# Echode.net
KiCad netlist of a schematic drawn in Altium Designer
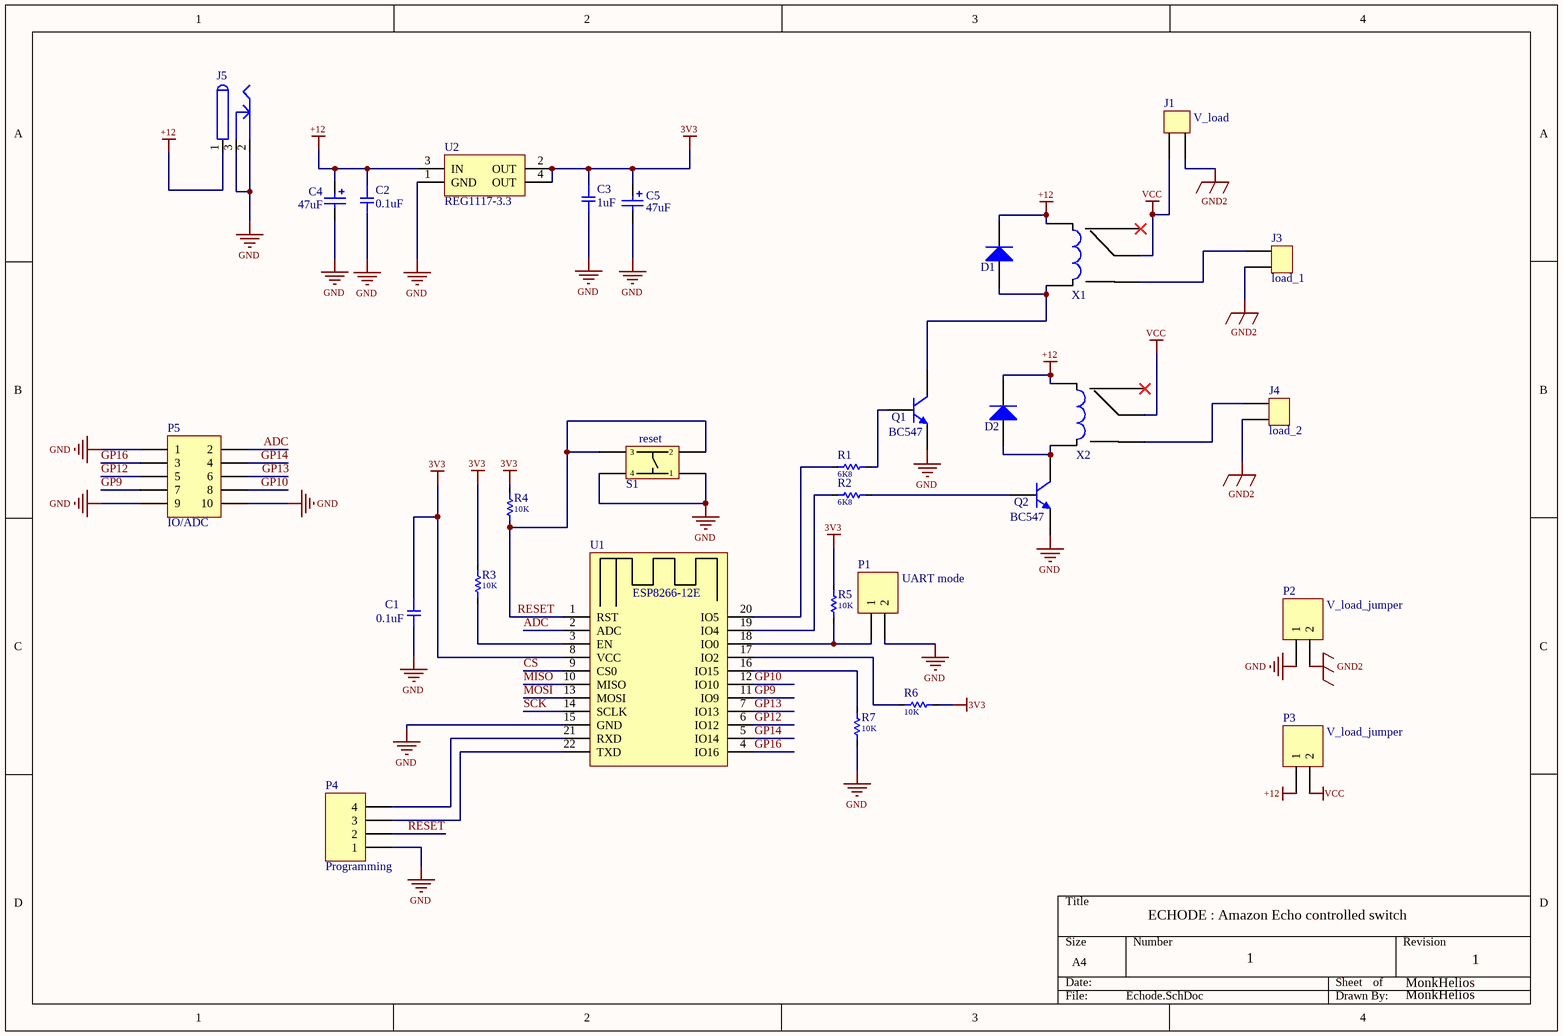
[diagram p0: Echode.SchDoc]

(export (version "E")
  (design (tool "Eeschema 10.0.6"))
  (components
    (comp (ref "C1")
      (value "0.1uF")
      (footprint "SMD-0805C")
      (description "CAP CER 10000PF 250V X7T 0805")
      (fields
        (field (name "DIGI-KEY PART NUMBER") "490-13986-1-ND")
        (field (name "PART NUMBER") "GC321AD72E103KX01D")
      )
      (libsource (lib "capacitor_murata_0805") (part "GC321AD72E103KX01D"))
    )
    (comp (ref "C2")
      (value "0.1uF")
      (footprint "SMD-0805C")
      (description "CAP CER 10000PF 250V X7T 0805")
      (fields
        (field (name "DIGI-KEY PART NUMBER") "490-13986-1-ND")
        (field (name "PART NUMBER") "GC321AD72E103KX01D")
      )
      (libsource (lib "capacitor_murata_0805") (part "GC321AD72E103KX01D"))
    )
    (comp (ref "C3")
      (value "1uF")
      (footprint "SMD-0805C")
      (description "CAP CER 10000PF 250V X7T 0805")
      (fields
        (field (name "DIGI-KEY PART NUMBER") "490-13986-1-ND")
        (field (name "PART NUMBER") "GC321AD72E103KX01D")
      )
      (libsource (lib "capacitor_murata_0805") (part "GC321AD72E103KX01D"))
    )
    (comp (ref "C4")
      (value "47uF")
      (footprint "PCBComponent_1")
      (libsource (lib "cap_pol") (part "Component_1"))
    )
    (comp (ref "C5")
      (value "47uF")
      (footprint "PCBComponent_1")
      (libsource (lib "cap_pol") (part "Component_1"))
    )
    (comp (ref "D1")
      (value "Diode 1N4007")
      (footprint "DO-41")
      (description "1 Amp General Purpose Rectifier")
      (fields (field (name "PUBLISHER") "Altium Limited"))
      (libsource (lib "Miscellaneous Devices") (part "Diode 1N4007"))
    )
    (comp (ref "D2")
      (value "Diode 1N4007")
      (footprint "DO-41")
      (description "1 Amp General Purpose Rectifier")
      (fields (field (name "PUBLISHER") "Altium Limited"))
      (libsource (lib "Miscellaneous Devices") (part "Diode 1N4007"))
    )
    (comp (ref "J1")
      (value "V_load")
      (footprint "Degson_DG126-5.0-02P-14")
      (libsource (lib "Degson_DG126-5.0-02P-14_Screw_Terminal") (part "Component_1"))
    )
    (comp (ref "J3")
      (value "load_1")
      (footprint "Degson_DG126-5.0-02P-14")
      (libsource (lib "") (part "Component_1_1"))
    )
    (comp (ref "J4")
      (value "load_2")
      (footprint "Degson_DG126-5.0-02P-14")
      (libsource (lib "") (part "Component_1_1"))
    )
    (comp (ref "J5")
      (value "PWR2.5")
      (footprint "KLD-0202")
      (description "Low Voltage Power Supply Connector")
      (fields (field (name "PUBLISHER") "Altium Limited"))
      (libsource (lib "Miscellaneous Connectors") (part "PWR2.5"))
    )
    (comp (ref "P1")
      (value "UART mode")
      (footprint "HDR1X2")
      (description "Header, 2-Pin")
      (fields (field (name "PUBLISHER") "Altium Limited"))
      (libsource (lib "Miscellaneous Connectors") (part "Header 2"))
    )
    (comp (ref "P2")
      (value "V_load_jumper")
      (footprint "HDR1X2")
      (description "Header, 2-Pin")
      (fields (field (name "PUBLISHER") "Altium Limited"))
      (libsource (lib "Miscellaneous Connectors") (part "Header 2"))
    )
    (comp (ref "P3")
      (value "V_load_jumper")
      (footprint "HDR1X2")
      (description "Header, 2-Pin")
      (fields (field (name "PUBLISHER") "Altium Limited"))
      (libsource (lib "Miscellaneous Connectors") (part "Header 2"))
    )
    (comp (ref "P4")
      (value "Programming")
      (footprint "HDR1X4")
      (description "Header, 4-Pin")
      (fields (field (name "PUBLISHER") "Altium Limited"))
      (libsource (lib "Miscellaneous Connectors") (part "Header 4"))
    )
    (comp (ref "P5")
      (value "IO/ADC")
      (footprint "HDR2X5")
      (description "Header, 5-Pin, Dual row")
      (fields (field (name "PUBLISHER") "Altium Limited"))
      (libsource (lib "Miscellaneous Connectors") (part "Header 5X2"))
    )
    (comp (ref "Q1")
      (value "BC547")
      (footprint "SOT-23B_N")
      (description "NPN Bipolar Transistor")
      (fields (field (name "PUBLISHER") "Altium Limited"))
      (libsource (lib "Miscellaneous Devices") (part "QNPN"))
    )
    (comp (ref "Q2")
      (value "BC547")
      (footprint "SOT-23B_N")
      (description "NPN Bipolar Transistor")
      (fields (field (name "PUBLISHER") "Altium Limited"))
      (libsource (lib "Miscellaneous Devices") (part "QNPN"))
    )
    (comp (ref "R1")
      (value "Component_1")
      (footprint "Resistor_0805")
      (fields (field (name "ALTIUM_UNNAMED_1") "6K8"))
      (libsource (lib "res") (part "Component_1"))
    )
    (comp (ref "R2")
      (value "Component_1")
      (footprint "Resistor_0805")
      (fields (field (name "ALTIUM_UNNAMED_1") "6K8"))
      (libsource (lib "res") (part "Component_1"))
    )
    (comp (ref "R3")
      (value "Component_1")
      (footprint "Resistor_0805")
      (fields (field (name "ALTIUM_UNNAMED_1") "10K"))
      (libsource (lib "res") (part "Component_1"))
    )
    (comp (ref "R4")
      (value "Component_1")
      (footprint "Resistor_0805")
      (fields (field (name "ALTIUM_UNNAMED_1") "10K"))
      (libsource (lib "res") (part "Component_1"))
    )
    (comp (ref "R5")
      (value "Component_1")
      (footprint "Resistor_0805")
      (fields (field (name "ALTIUM_UNNAMED_1") "10K"))
      (libsource (lib "res") (part "Component_1"))
    )
    (comp (ref "R6")
      (value "Component_1")
      (footprint "Resistor_0805")
      (fields (field (name "ALTIUM_UNNAMED_1") "10K"))
      (libsource (lib "res") (part "Component_1"))
    )
    (comp (ref "R7")
      (value "Component_1")
      (footprint "Resistor_0805")
      (fields (field (name "ALTIUM_UNNAMED_1") "10K"))
      (libsource (lib "res") (part "Component_1"))
    )
    (comp (ref "S1")
      (value "reset")
      (footprint "PCBComponent_1")
      (libsource (lib "panasonic_90deg_tactile") (part "Component_1"))
    )
    (comp (ref "U1")
      (value "ESP8266-12E")
      (footprint "PCBComponent_1")
      (libsource (lib "ESP8266-12E") (part "ESP8266-12E"))
    )
    (comp (ref "U2")
      (value "REG1117-3.3")
      (footprint "ZZ311")
      (description "800mA and 1A Low Dropout Positive Regulator 2.85V, 3.3V, 5V, and Adjustable")
      (fields (field (name "PUBLISHER") "Altium Limited"))
      (libsource (lib "BB Power Mgt Voltage Regulator") (part "REG1117-3.3"))
    )
    (comp (ref "X1") (value "~") (footprint "845HN-1C-C") (libsource (lib "845HN-1C-C") (part "845HN-1C-C")))
    (comp (ref "X2") (value "~") (footprint "845HN-1C-C") (libsource (lib "845HN-1C-C") (part "845HN-1C-C")))
  )
  (nets
    (net (code "1") (name "+12") (class "Default")
      (node (ref "C2") (pin "1") (pinfunction "1_1") (pintype "passive"))
      (node (ref "C4") (pin "1") (pinfunction "1_1") (pintype "passive"))
      (node (ref "D1") (pin "2") (pinfunction "K_2") (pintype "passive"))
      (node (ref "D2") (pin "2") (pinfunction "K_2") (pintype "passive"))
      (node (ref "J5") (pin "1") (pinfunction "1_1") (pintype "power_in"))
      (node (ref "P3") (pin "1") (pinfunction "1_1") (pintype "passive"))
      (node (ref "U2") (pin "3") (pinfunction "IN_3") (pintype "power_in"))
      (node (ref "X1") (pin "1") (pinfunction "1_1") (pintype "passive"))
      (node (ref "X2") (pin "1") (pinfunction "1_1") (pintype "passive"))
    )
    (net (code "2") (name "/ADC") (class "Default")
      (node (ref "P5") (pin "2") (pinfunction "2_2") (pintype "passive"))
      (node (ref "U1") (pin "2") (pinfunction "ADC_2") (pintype "passive"))
    )
    (net (code "3") (name "/CS") (class "Default")
      (node (ref "U1") (pin "9") (pinfunction "CS0_9") (pintype "passive"))
    )
    (net (code "4") (name "/GP9") (class "Default")
      (node (ref "P5") (pin "7") (pinfunction "7_7") (pintype "passive"))
      (node (ref "U1") (pin "11") (pinfunction "IO9_11") (pintype "passive"))
    )
    (net (code "5") (name "/GP10") (class "Default")
      (node (ref "P5") (pin "8") (pinfunction "8_8") (pintype "passive"))
      (node (ref "U1") (pin "12") (pinfunction "IO10_12") (pintype "passive"))
    )
    (net (code "6") (name "/GP12") (class "Default")
      (node (ref "P5") (pin "5") (pinfunction "5_5") (pintype "passive"))
      (node (ref "U1") (pin "6") (pinfunction "IO12_6") (pintype "passive"))
    )
    (net (code "7") (name "/GP13") (class "Default")
      (node (ref "P5") (pin "6") (pinfunction "6_6") (pintype "passive"))
      (node (ref "U1") (pin "7") (pinfunction "IO13_7") (pintype "passive"))
    )
    (net (code "8") (name "/GP14") (class "Default")
      (node (ref "P5") (pin "4") (pinfunction "4_4") (pintype "passive"))
      (node (ref "U1") (pin "5") (pinfunction "IO14_5") (pintype "passive"))
    )
    (net (code "9") (name "/GP16") (class "Default")
      (node (ref "P5") (pin "3") (pinfunction "3_3") (pintype "passive"))
      (node (ref "U1") (pin "4") (pinfunction "IO16_4") (pintype "passive"))
    )
    (net (code "10") (name "/MISO") (class "Default")
      (node (ref "U1") (pin "10") (pinfunction "MISO_10") (pintype "passive"))
    )
    (net (code "11") (name "/MOSI") (class "Default")
      (node (ref "U1") (pin "13") (pinfunction "MOSI_13") (pintype "passive"))
    )
    (net (code "12") (name "/RESET") (class "Default")
      (node (ref "P4") (pin "2") (pinfunction "2_2") (pintype "passive"))
      (node (ref "R4") (pin "1") (pinfunction "1_1") (pintype "passive"))
      (node (ref "S1") (pin "2") (pinfunction "2_2") (pintype "passive"))
      (node (ref "S1") (pin "3") (pinfunction "3_3") (pintype "passive"))
      (node (ref "U1") (pin "1") (pinfunction "RST_1") (pintype "passive"))
    )
    (net (code "13") (name "/SCK") (class "Default")
      (node (ref "U1") (pin "14") (pinfunction "SCLK_14") (pintype "passive"))
    )
    (net (code "14") (name "3V3") (class "Default")
      (node (ref "C1") (pin "1") (pinfunction "1_1") (pintype "passive"))
      (node (ref "C3") (pin "1") (pinfunction "1_1") (pintype "passive"))
      (node (ref "C5") (pin "1") (pinfunction "1_1") (pintype "passive"))
      (node (ref "R3") (pin "2") (pinfunction "2_2") (pintype "passive"))
      (node (ref "R4") (pin "2") (pinfunction "2_2") (pintype "passive"))
      (node (ref "R5") (pin "1") (pinfunction "1_1") (pintype "passive"))
      (node (ref "R6") (pin "1") (pinfunction "1_1") (pintype "passive"))
      (node (ref "U1") (pin "8") (pinfunction "VCC_8") (pintype "passive"))
      (node (ref "U2") (pin "2") (pinfunction "OUT_2") (pintype "power_in"))
      (node (ref "U2") (pin "4") (pinfunction "OUT_4") (pintype "power_in"))
    )
    (net (code "15") (name "GND") (class "Default")
      (node (ref "C1") (pin "2") (pinfunction "2_2") (pintype "passive"))
      (node (ref "C2") (pin "2") (pinfunction "2_2") (pintype "passive"))
      (node (ref "C3") (pin "2") (pinfunction "2_2") (pintype "passive"))
      (node (ref "C4") (pin "2") (pinfunction "2_2") (pintype "passive"))
      (node (ref "C5") (pin "2") (pinfunction "2_2") (pintype "passive"))
      (node (ref "J5") (pin "2") (pinfunction "2_2") (pintype "power_in"))
      (node (ref "J5") (pin "3") (pinfunction "3_3") (pintype "power_in"))
      (node (ref "P1") (pin "2") (pinfunction "2_2") (pintype "passive"))
      (node (ref "P2") (pin "1") (pinfunction "1_1") (pintype "passive"))
      (node (ref "P4") (pin "1") (pinfunction "1_1") (pintype "passive"))
      (node (ref "P5") (pin "1") (pinfunction "1_1") (pintype "passive"))
      (node (ref "P5") (pin "10") (pinfunction "10_10") (pintype "passive"))
      (node (ref "P5") (pin "9") (pinfunction "9_9") (pintype "passive"))
      (node (ref "Q1") (pin "3") (pinfunction "E_3") (pintype "passive"))
      (node (ref "Q2") (pin "3") (pinfunction "E_3") (pintype "passive"))
      (node (ref "R7") (pin "1") (pinfunction "1_1") (pintype "passive"))
      (node (ref "S1") (pin "1") (pinfunction "1_1") (pintype "passive"))
      (node (ref "S1") (pin "4") (pinfunction "4_4") (pintype "passive"))
      (node (ref "U1") (pin "15") (pinfunction "GND_15") (pintype "passive"))
      (node (ref "U2") (pin "1") (pinfunction "GND_1") (pintype "power_in"))
    )
    (net (code "16") (name "GND2") (class "Default")
      (node (ref "J1") (pin "2") (pinfunction "2_2") (pintype "passive"))
      (node (ref "J3") (pin "2") (pinfunction "2_2") (pintype "passive"))
      (node (ref "J4") (pin "2") (pinfunction "2_2") (pintype "passive"))
      (node (ref "P2") (pin "2") (pinfunction "2_2") (pintype "passive"))
    )
    (net (code "17") (name "Net-(D1-A)") (class "Default")
      (node (ref "D1") (pin "1") (pinfunction "A_1") (pintype "passive"))
      (node (ref "Q1") (pin "1") (pinfunction "C_1") (pintype "passive"))
      (node (ref "X1") (pin "2") (pinfunction "2_2") (pintype "passive"))
    )
    (net (code "18") (name "Net-(D2-A)") (class "Default")
      (node (ref "D2") (pin "1") (pinfunction "A_1") (pintype "passive"))
      (node (ref "Q2") (pin "1") (pinfunction "C_1") (pintype "passive"))
      (node (ref "X2") (pin "2") (pinfunction "2_2") (pintype "passive"))
    )
    (net (code "19") (name "Net-(J3-Pad1)") (class "Default")
      (node (ref "J3") (pin "1") (pinfunction "1_1") (pintype "passive"))
      (node (ref "X1") (pin "5") (pinfunction "5_5") (pintype "passive"))
    )
    (net (code "20") (name "Net-(J4-Pad1)") (class "Default")
      (node (ref "J4") (pin "1") (pinfunction "1_1") (pintype "passive"))
      (node (ref "X2") (pin "5") (pinfunction "5_5") (pintype "passive"))
    )
    (net (code "21") (name "Net-(Q1-B)") (class "Default")
      (node (ref "Q1") (pin "2") (pinfunction "B_2") (pintype "passive"))
      (node (ref "R1") (pin "2") (pinfunction "2_2") (pintype "passive"))
    )
    (net (code "22") (name "Net-(Q2-B)") (class "Default")
      (node (ref "Q2") (pin "2") (pinfunction "B_2") (pintype "passive"))
      (node (ref "R2") (pin "2") (pinfunction "2_2") (pintype "passive"))
    )
    (net (code "23") (name "Net-(U1-EN)") (class "Default")
      (node (ref "R3") (pin "1") (pinfunction "1_1") (pintype "passive"))
      (node (ref "U1") (pin "3") (pinfunction "EN_3") (pintype "passive"))
    )
    (net (code "24") (name "Net-(U1-IO0)") (class "Default")
      (node (ref "P1") (pin "1") (pinfunction "1_1") (pintype "passive"))
      (node (ref "R5") (pin "2") (pinfunction "2_2") (pintype "passive"))
      (node (ref "U1") (pin "18") (pinfunction "IO0_18") (pintype "passive"))
    )
    (net (code "25") (name "Net-(U1-IO2)") (class "Default")
      (node (ref "R6") (pin "2") (pinfunction "2_2") (pintype "passive"))
      (node (ref "U1") (pin "17") (pinfunction "IO2_17") (pintype "passive"))
    )
    (net (code "26") (name "Net-(U1-IO4)") (class "Default")
      (node (ref "R2") (pin "1") (pinfunction "1_1") (pintype "passive"))
      (node (ref "U1") (pin "19") (pinfunction "IO4_19") (pintype "passive"))
    )
    (net (code "27") (name "Net-(U1-IO5)") (class "Default")
      (node (ref "R1") (pin "1") (pinfunction "1_1") (pintype "passive"))
      (node (ref "U1") (pin "20") (pinfunction "IO5_20") (pintype "passive"))
    )
    (net (code "28") (name "Net-(U1-IO15)") (class "Default")
      (node (ref "R7") (pin "2") (pinfunction "2_2") (pintype "passive"))
      (node (ref "U1") (pin "16") (pinfunction "IO15_16") (pintype "passive"))
    )
    (net (code "29") (name "Net-(U1-RXD)") (class "Default")
      (node (ref "P4") (pin "4") (pinfunction "4_4") (pintype "passive"))
      (node (ref "U1") (pin "21") (pinfunction "RXD_21") (pintype "passive"))
    )
    (net (code "30") (name "Net-(U1-TXD)") (class "Default")
      (node (ref "P4") (pin "3") (pinfunction "3_3") (pintype "passive"))
      (node (ref "U1") (pin "22") (pinfunction "TXD_22") (pintype "passive"))
    )
    (net (code "31") (name "VCC") (class "Default")
      (node (ref "J1") (pin "1") (pinfunction "1_1") (pintype "passive"))
      (node (ref "P3") (pin "2") (pinfunction "2_2") (pintype "passive"))
      (node (ref "X1") (pin "4") (pinfunction "4_4") (pintype "passive"))
      (node (ref "X2") (pin "4") (pinfunction "4_4") (pintype "passive"))
    )
    (net (code "32") (name "unconnected-(X1-Pad3)") (class "Default")
      (node (ref "X1") (pin "3") (pinfunction "3_3") (pintype "passive+no_connect"))
    )
    (net (code "33") (name "unconnected-(X2-Pad3)") (class "Default")
      (node (ref "X2") (pin "3") (pinfunction "3_3") (pintype "passive+no_connect"))
    )
  )
)
